# AutoTuner.net
KiCad netlist of a schematic drawn in EAGLE
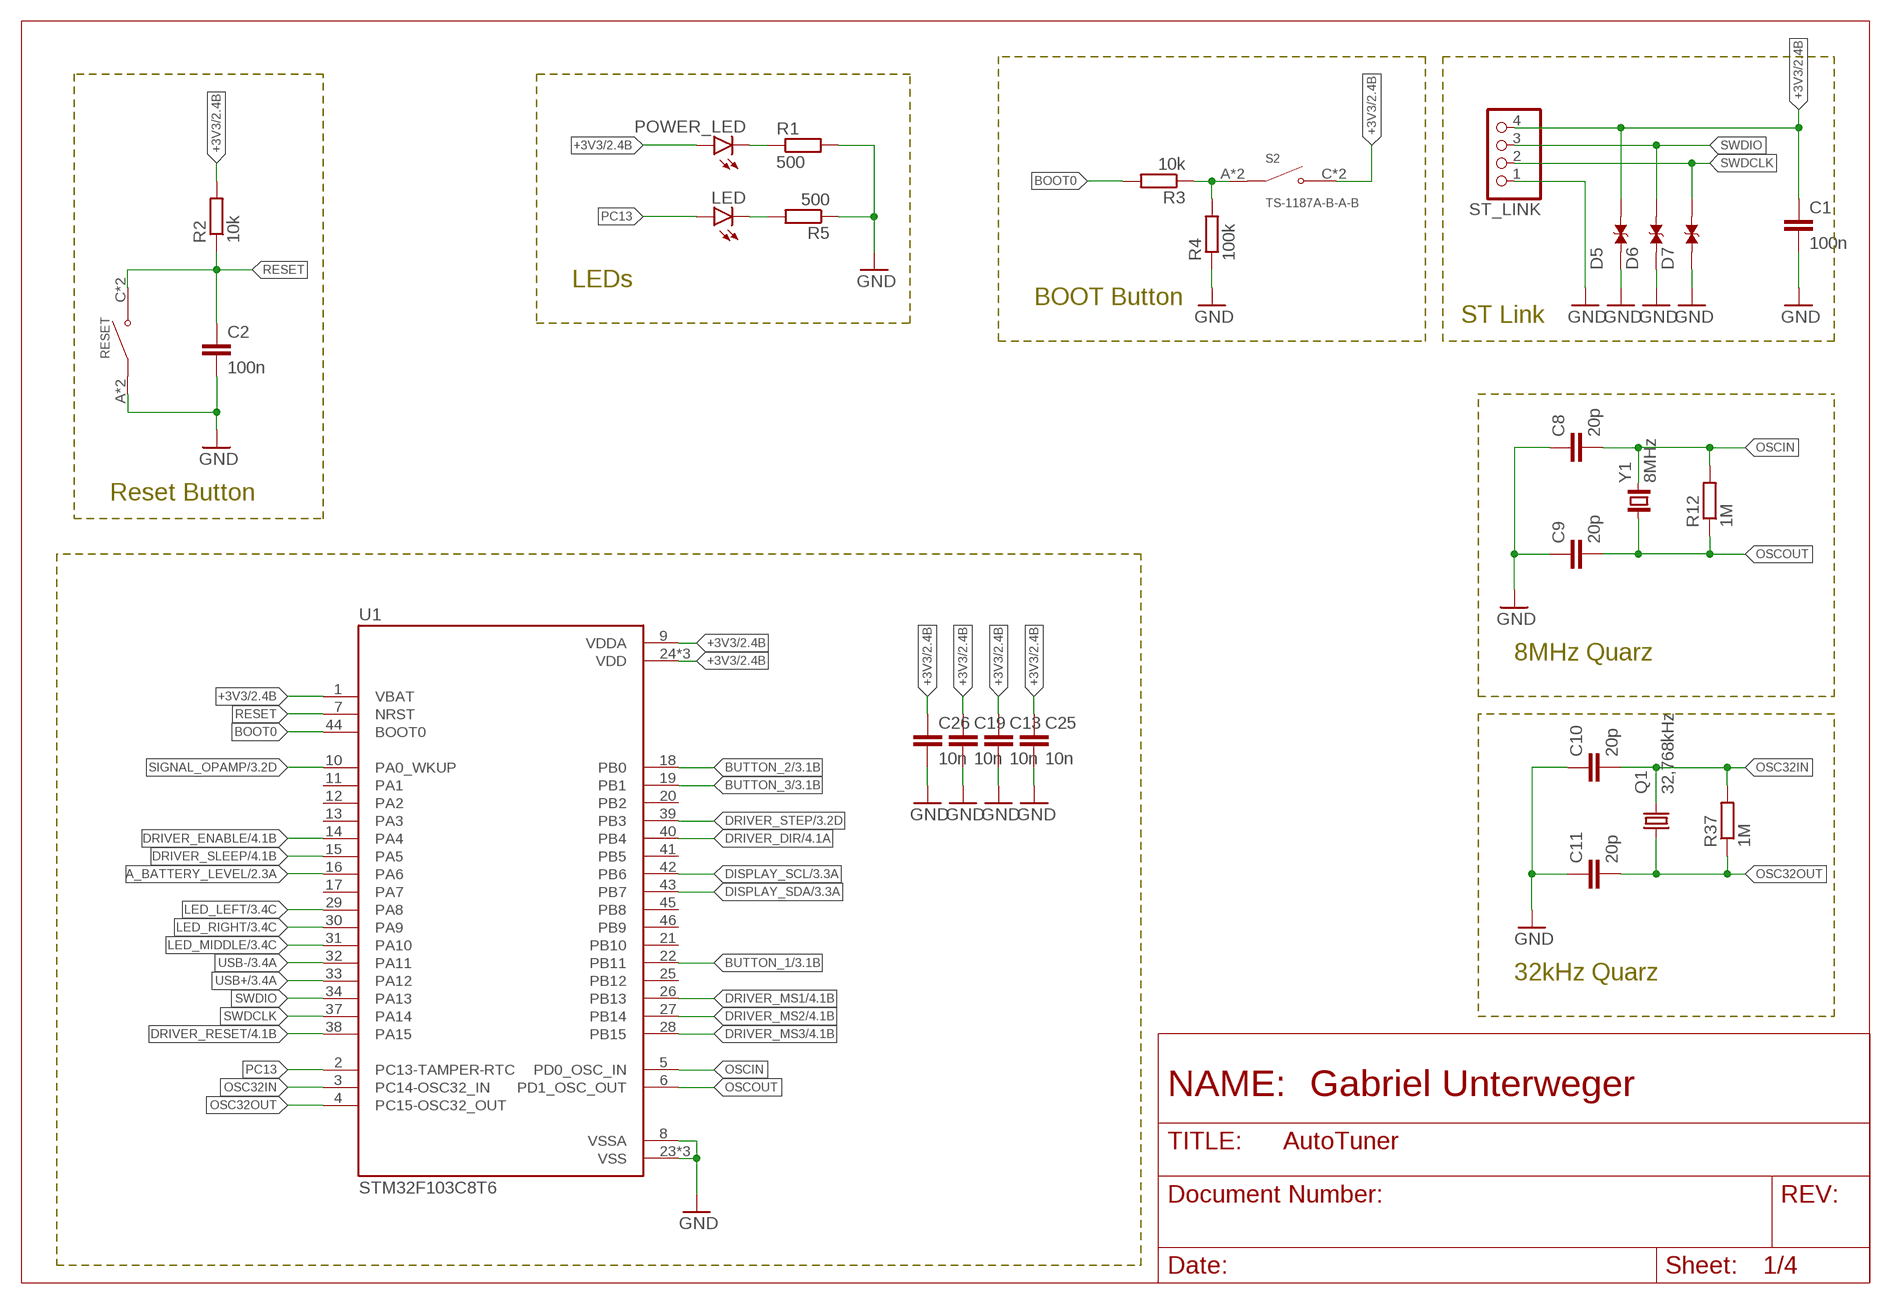
[diagram p0: schematic, sheet 1]
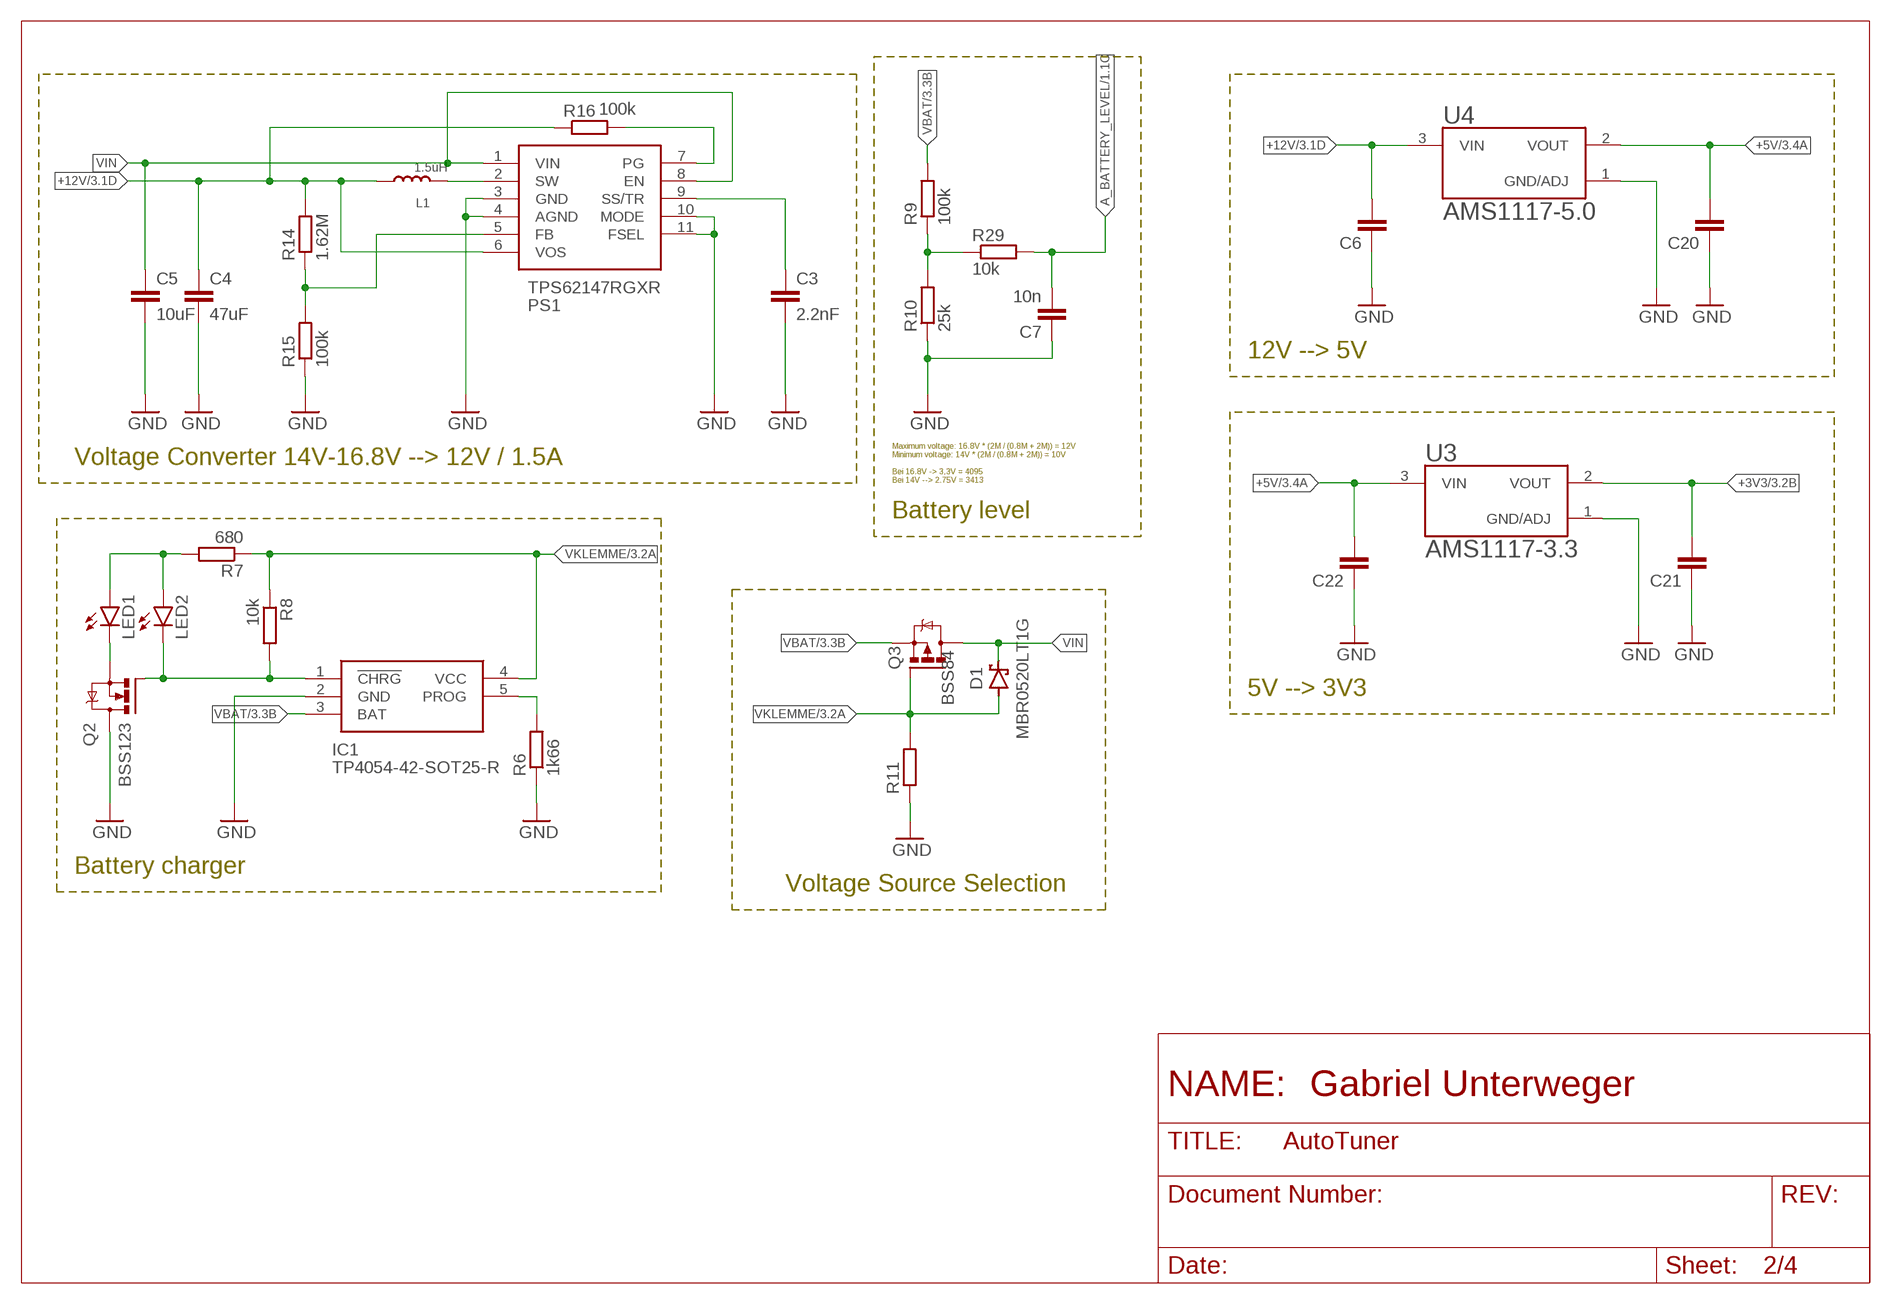
[diagram p1: schematic, sheet 2]
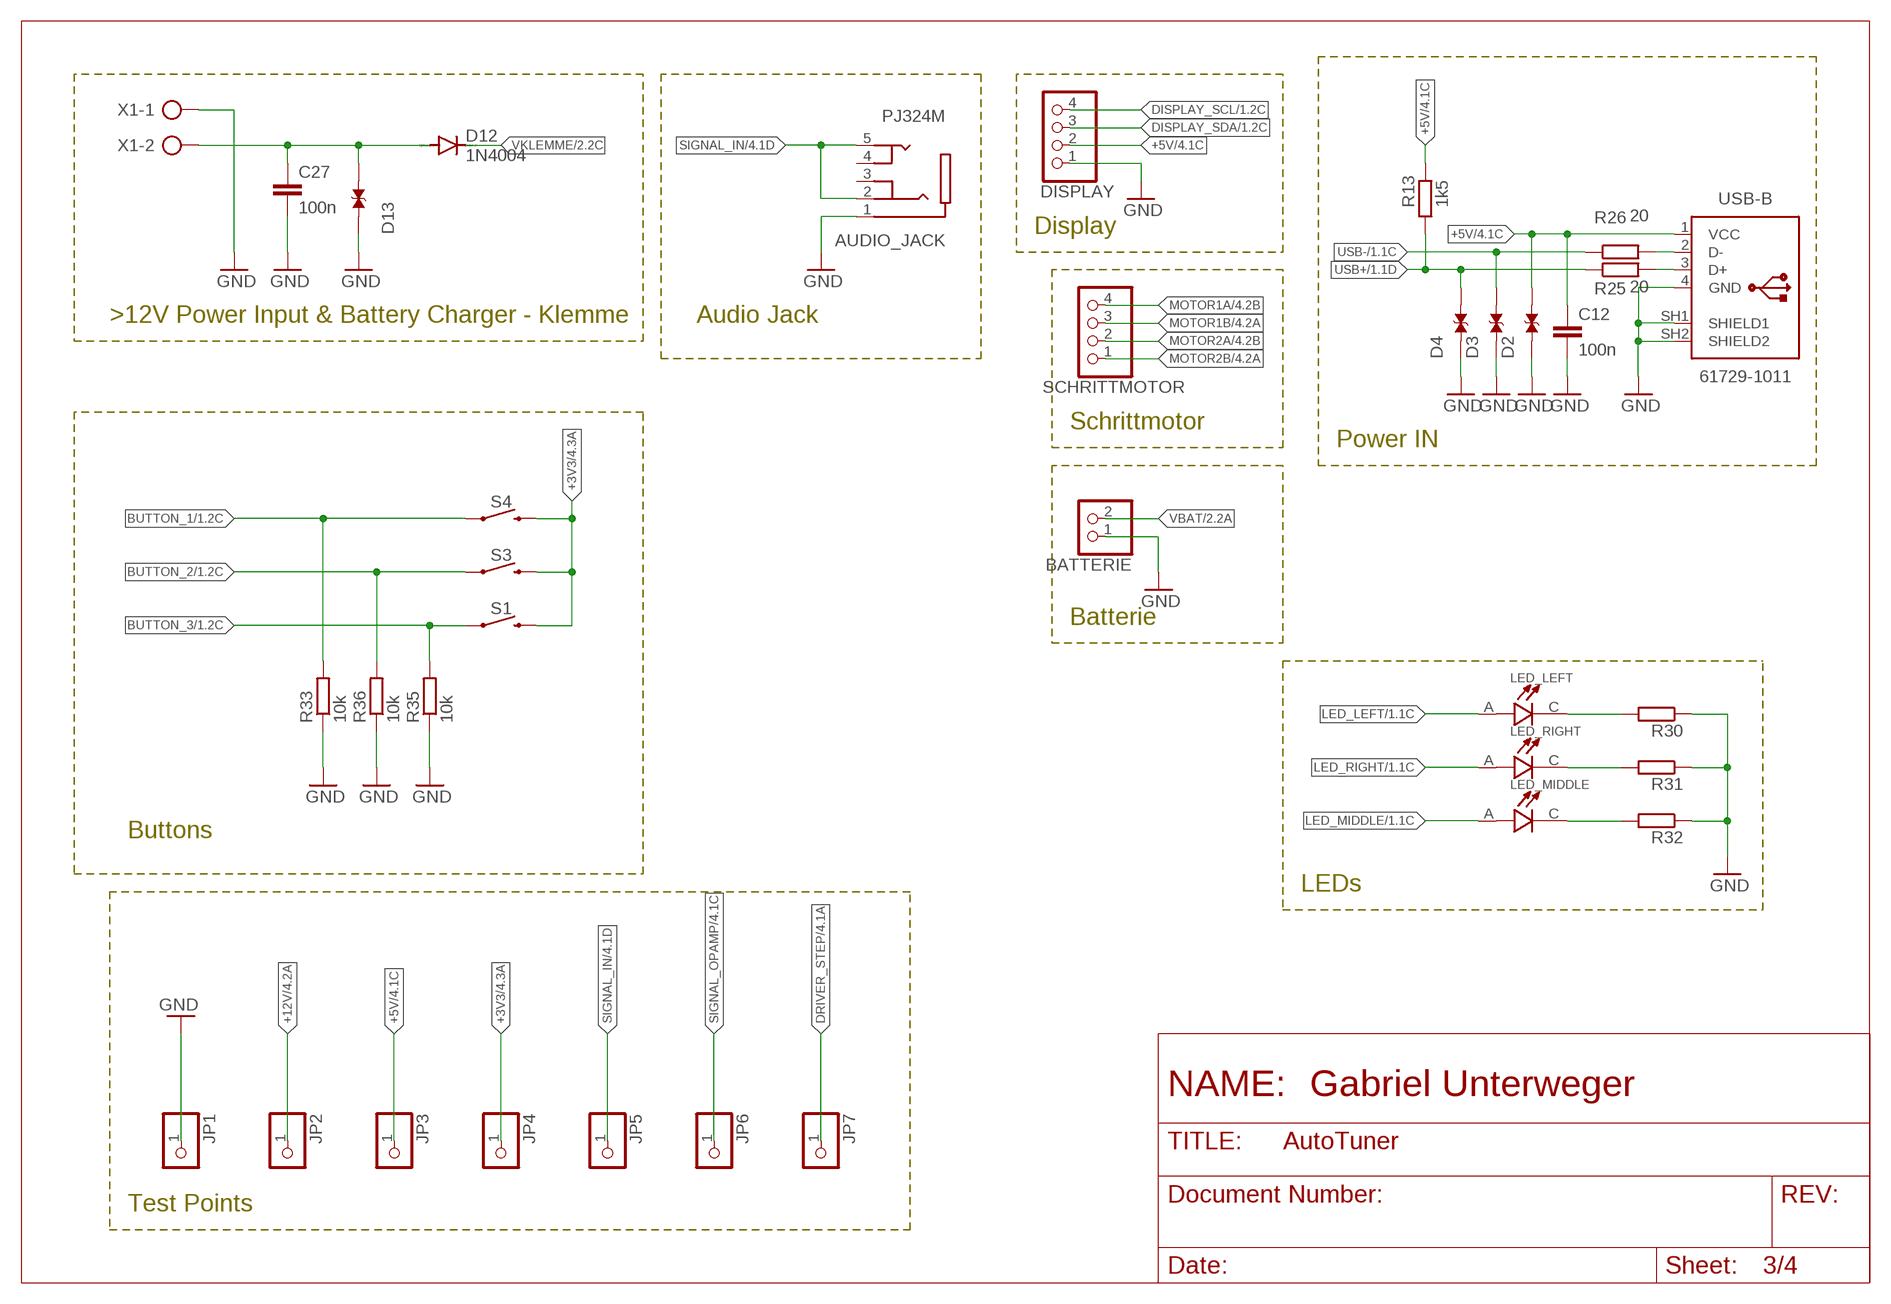
[diagram p2: schematic, sheet 3]
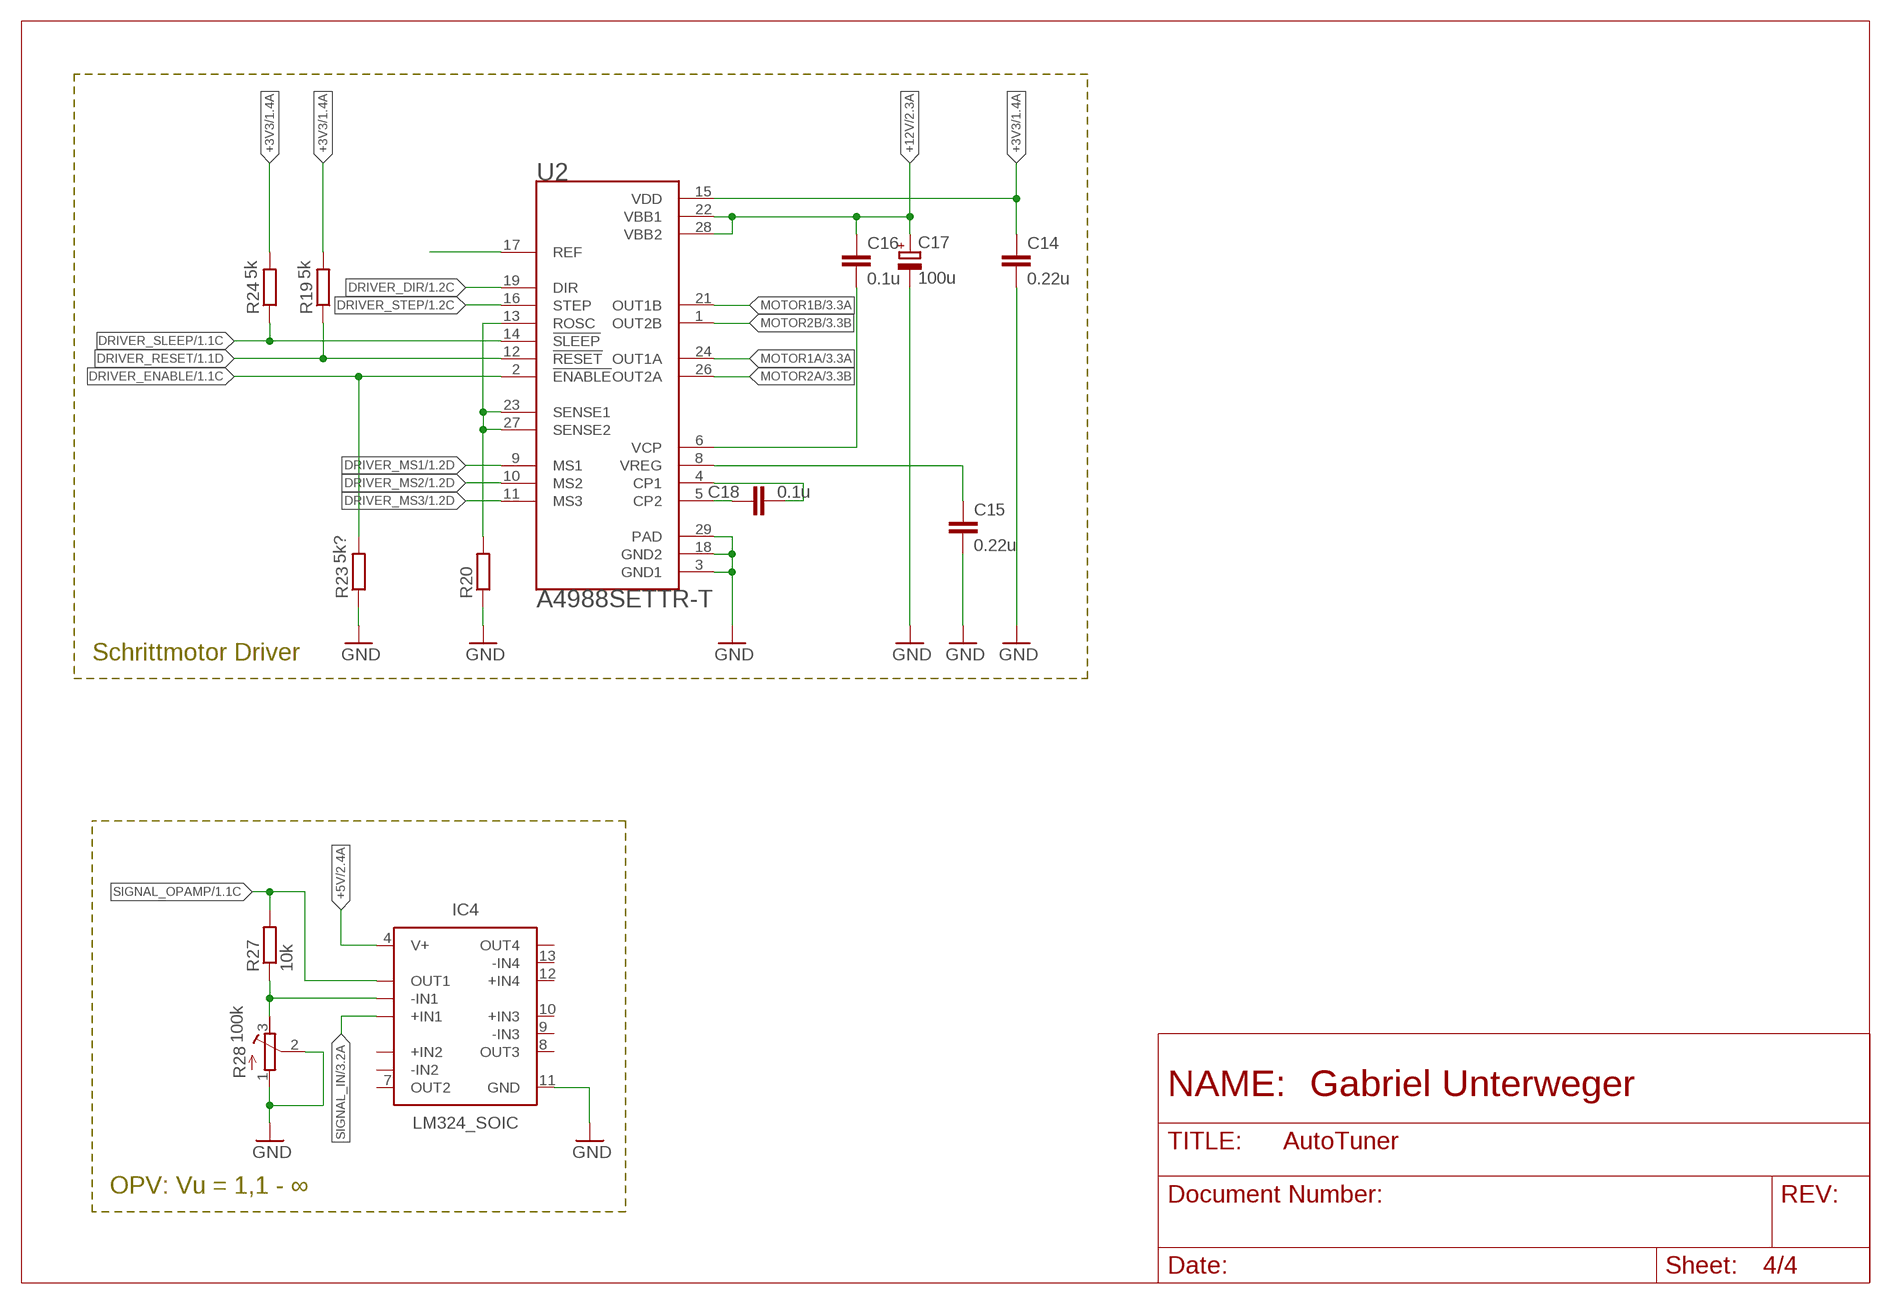
[diagram p3: schematic, sheet 4]

(export (version "E")
  (design (tool "Eeschema 10.0.6"))
  (components
    (comp (ref "C1")
      (value "100n")
      (footprint "eagle-import:C0805")
      (libsource (lib "eagle-import") (part "C-EUC0805"))
    )
    (comp (ref "C2")
      (value "100n")
      (footprint "eagle-import:C0805")
      (libsource (lib "eagle-import") (part "C-EUC0805"))
    )
    (comp (ref "C8")
      (value "20p")
      (footprint "eagle-import:C0805")
      (libsource (lib "eagle-import") (part "C-EUC0805"))
    )
    (comp (ref "C9")
      (value "20p")
      (footprint "eagle-import:C0805")
      (libsource (lib "eagle-import") (part "C-EUC0805"))
    )
    (comp (ref "C10")
      (value "20p")
      (footprint "eagle-import:C0805")
      (libsource (lib "eagle-import") (part "C-EUC0805"))
    )
    (comp (ref "C11")
      (value "20p")
      (footprint "eagle-import:C0805")
      (libsource (lib "eagle-import") (part "C-EUC0805"))
    )
    (comp (ref "C13")
      (value "10n")
      (footprint "eagle-import:C0805")
      (libsource (lib "eagle-import") (part "C-EUC0805"))
    )
    (comp (ref "C19")
      (value "10n")
      (footprint "eagle-import:C0805")
      (libsource (lib "eagle-import") (part "C-EUC0805"))
    )
    (comp (ref "C25")
      (value "10n")
      (footprint "eagle-import:C0805")
      (libsource (lib "eagle-import") (part "C-EUC0805"))
    )
    (comp (ref "C26")
      (value "10n")
      (footprint "eagle-import:C0805")
      (libsource (lib "eagle-import") (part "C-EUC0805"))
    )
    (comp (ref "D5")
      (value "TESD5V0L1UC_RJG")
      (footprint "eagle-import:DIO_TESD5V0L1UC_RJG")
      (fields (field (name "MF") "Taiwan Semiconductor Corporation") (field (name "MP") "TESD5V0L1UC RJG"))
      (libsource (lib "eagle-import") (part "TESD5V0L1UC_RJG"))
    )
    (comp (ref "D6")
      (value "TESD5V0L1UC_RJG")
      (footprint "eagle-import:DIO_TESD5V0L1UC_RJG")
      (fields (field (name "MF") "Taiwan Semiconductor Corporation") (field (name "MP") "TESD5V0L1UC RJG"))
      (libsource (lib "eagle-import") (part "TESD5V0L1UC_RJG"))
    )
    (comp (ref "D7")
      (value "TESD5V0L1UC_RJG")
      (footprint "eagle-import:DIO_TESD5V0L1UC_RJG")
      (fields
        (field (name "MF") "Taiwan Semiconductor Corporation")
        (field (name "MP") "TESD5V0L1UC RJG")
        (field (name "LCSC_PART") "C7420372")
      )
      (libsource (lib "eagle-import") (part "TESD5V0L1UC_RJG"))
    )
    (comp (ref "LED")
      (value "LEDCHIPLED_0805")
      (footprint "eagle-import:CHIPLED_0805")
      (libsource (lib "eagle-import") (part "LEDCHIPLED_0805"))
    )
    (comp (ref "POWER_LED")
      (value "LEDCHIPLED_0805")
      (footprint "eagle-import:CHIPLED_0805")
      (libsource (lib "eagle-import") (part "LEDCHIPLED_0805"))
    )
    (comp (ref "Q1")
      (value "32,768kHz")
      (footprint "eagle-import:3.2X1.5")
      (fields (field (name "LCSC_PART") "C32346"))
      (libsource (lib "eagle-import") (part "KX-327-NHF"))
    )
    (comp (ref "R1")
      (value "500")
      (footprint "eagle-import:R0805")
      (libsource (lib "eagle-import") (part "R-EU_R0805"))
    )
    (comp (ref "R2")
      (value "10k")
      (footprint "eagle-import:R0805")
      (libsource (lib "eagle-import") (part "R-EU_R0805"))
    )
    (comp (ref "R3")
      (value "10k")
      (footprint "eagle-import:R0805")
      (libsource (lib "eagle-import") (part "R-EU_R0805"))
    )
    (comp (ref "R4")
      (value "100k")
      (footprint "eagle-import:R0805")
      (libsource (lib "eagle-import") (part "R-EU_R0805"))
    )
    (comp (ref "R5")
      (value "500")
      (footprint "eagle-import:R0805")
      (libsource (lib "eagle-import") (part "R-EU_R0805"))
    )
    (comp (ref "R12")
      (value "1M")
      (footprint "eagle-import:R0805")
      (libsource (lib "eagle-import") (part "R-EU_R0805"))
    )
    (comp (ref "R37")
      (value "1M")
      (footprint "eagle-import:R0805")
      (libsource (lib "eagle-import") (part "R-EU_R0805"))
    )
    (comp (ref "RESET")
      (value "TS-1187A-B-A-B")
      (footprint "eagle-import:SW_TS-1187A-B-A-B")
      (fields (field (name "MF") "XKB Industrial Precision") (field (name "LCSC_PART") "C318884"))
      (libsource (lib "eagle-import") (part "TS-1187A-B-A-B"))
    )
    (comp (ref "S2")
      (value "TS-1187A-B-A-B")
      (footprint "eagle-import:SW_TS-1187A-B-A-B")
      (fields (field (name "MF") "XKB Industrial Precision") (field (name "LCSC_PART") "C318884"))
      (libsource (lib "eagle-import") (part "TS-1187A-B-A-B"))
    )
    (comp (ref "ST_LINK")
      (value "PINHD-1X4")
      (footprint "eagle-import:1X04")
      (libsource (lib "eagle-import") (part "PINHD-1X4"))
    )
    (comp (ref "U1")
      (value "STM32F103C8T6")
      (footprint "eagle-import:QFP50P900X900X160-48N")
      (fields (field (name "MF") "STMicroelectronics") (field (name "LCSC_PART") "C8734"))
      (libsource (lib "eagle-import") (part "STM32F103C8T6"))
    )
    (comp (ref "Y1")
      (value "8MHz")
      (footprint "eagle-import:CRYSTAL_2-SMD-5X3")
      (fields (field (name "LCSC_PART") "C115962"))
      (libsource (lib "eagle-import") (part "CRYSTAL_NX5032GA"))
    )
    (comp (ref "C14")
      (value "0.22u")
      (footprint "eagle-import:C0805")
      (libsource (lib "eagle-import") (part "C-EUC0805"))
    )
    (comp (ref "C15")
      (value "0.22u")
      (footprint "eagle-import:C0805")
      (libsource (lib "eagle-import") (part "C-EUC0805"))
    )
    (comp (ref "C16")
      (value "0.1u")
      (footprint "eagle-import:C0805")
      (libsource (lib "eagle-import") (part "C-EUC0805"))
    )
    (comp (ref "C17")
      (value "100u")
      (footprint "eagle-import:085CS_1AR")
      (libsource (lib "eagle-import") (part "CPOL-EU085CS-1AR"))
    )
    (comp (ref "C18")
      (value "0.1u")
      (footprint "eagle-import:C0805")
      (libsource (lib "eagle-import") (part "C-EUC0805"))
    )
    (comp (ref "IC4")
      (value "LM324_SOIC")
      (footprint "eagle-import:SOIC127P600X175-14N")
      (fields (field (name "MANUFACTURER") "Generic") (field (name "LCSC_PART") "C71035"))
      (libsource (lib "eagle-import") (part "LM324_SOIC"))
    )
    (comp (ref "R19")
      (value "5k")
      (footprint "eagle-import:R0805")
      (libsource (lib "eagle-import") (part "R-EU_R0805"))
    )
    (comp (ref "R20")
      (value "R-EU_R0805")
      (footprint "eagle-import:R0805")
      (libsource (lib "eagle-import") (part "R-EU_R0805"))
    )
    (comp (ref "R23")
      (value "5k?")
      (footprint "eagle-import:R0805")
      (libsource (lib "eagle-import") (part "R-EU_R0805"))
    )
    (comp (ref "R24")
      (value "5k")
      (footprint "eagle-import:R0805")
      (libsource (lib "eagle-import") (part "R-EU_R0805"))
    )
    (comp (ref "R27")
      (value "10k")
      (footprint "eagle-import:R0805")
      (libsource (lib "eagle-import") (part "R-EU_R0805"))
    )
    (comp (ref "R28")
      (value "100k")
      (footprint "eagle-import:RTRIM3296X")
      (libsource (lib "eagle-import") (part "R-TRIMM3296X"))
    )
    (comp (ref "U2")
      (value "A4988SETTR-T")
      (footprint "eagle-import:QFN50P500X500X90-29N")
      (fields (field (name "MF") "Allegro"))
      (libsource (lib "eagle-import") (part "A4988SETTR-T"))
    )
    (comp (ref "C3")
      (value "2.2nF")
      (footprint "eagle-import:C0805")
      (libsource (lib "eagle-import") (part "C-EUC0805"))
    )
    (comp (ref "C4")
      (value "47uF")
      (footprint "eagle-import:C0805")
      (libsource (lib "eagle-import") (part "C-EUC0805"))
    )
    (comp (ref "C5")
      (value "10uF")
      (footprint "eagle-import:C0805")
      (libsource (lib "eagle-import") (part "C-EUC0805"))
    )
    (comp (ref "C6")
      (value "C-EUC0805")
      (footprint "eagle-import:C0805")
      (libsource (lib "eagle-import") (part "C-EUC0805"))
    )
    (comp (ref "C7")
      (value "10n")
      (footprint "eagle-import:C0805")
      (libsource (lib "eagle-import") (part "C-EUC0805"))
    )
    (comp (ref "C20")
      (value "C-EUC0805")
      (footprint "eagle-import:C0805")
      (libsource (lib "eagle-import") (part "C-EUC0805"))
    )
    (comp (ref "C21")
      (value "C-EUC0805")
      (footprint "eagle-import:C0805")
      (libsource (lib "eagle-import") (part "C-EUC0805"))
    )
    (comp (ref "C22")
      (value "C-EUC0805")
      (footprint "eagle-import:C0805")
      (libsource (lib "eagle-import") (part "C-EUC0805"))
    )
    (comp (ref "D1")
      (value "MBR0520LT1G")
      (footprint "eagle-import:SODFL3718X115")
      (fields (field (name "MANUFACTURER") "ON Semiconductor") (field (name "LCSC_PART") "C191023"))
      (libsource (lib "eagle-import") (part "SCHOTTKY_DO-219MBR0520LT1G"))
    )
    (comp (ref "IC1")
      (value "TP4054-42-SOT25-R")
      (footprint "eagle-import:SOT95P280X100-5N")
      (fields (field (name "LCSC_PART") "C32574"))
      (libsource (lib "eagle-import") (part "TP4054-42-SOT25-R"))
    )
    (comp (ref "L1")
      (value "1.5uH")
      (footprint "eagle-import:PSPCAQ54")
      (fields (field (name "LCSC_PART") "C2686105"))
      (libsource (lib "eagle-import") (part "PSPCAQ54"))
    )
    (comp (ref "LED1")
      (value "LEDCHIPLED_0805")
      (footprint "eagle-import:CHIPLED_0805")
      (libsource (lib "eagle-import") (part "LEDCHIPLED_0805"))
    )
    (comp (ref "LED2")
      (value "LEDCHIPLED_0805")
      (footprint "eagle-import:CHIPLED_0805")
      (libsource (lib "eagle-import") (part "LEDCHIPLED_0805"))
    )
    (comp (ref "PS1")
      (value "TPS62147RGXR")
      (footprint "eagle-import:TPS621361RGXT")
      (fields (field (name "MOUSER_PART_NUMBER") "595-TPS62147RGXR"))
      (libsource (lib "eagle-import") (part "TPS62147RGXR"))
    )
    (comp (ref "Q2")
      (value "BSS123")
      (footprint "eagle-import:SOT23")
      (fields
        (field (name "MANUFACTURER") "ON Semiconductor")
        (field (name "MPN") "BSS123L")
        (field (name "LCSC_PART") "C20917")
      )
      (libsource (lib "eagle-import") (part "NMOSFET__SOT23-GSDBSS123"))
    )
    (comp (ref "Q3")
      (value "BSS84")
      (footprint "eagle-import:SOT23")
      (fields (field (name "MANUFACTURER") "ON Semiconductor"))
      (libsource (lib "eagle-import") (part "PMOSFET__SOT23-GSDBSS84"))
    )
    (comp (ref "R6")
      (value "1k66")
      (footprint "eagle-import:R0805")
      (libsource (lib "eagle-import") (part "R-EU_R0805"))
    )
    (comp (ref "R7")
      (value "680")
      (footprint "eagle-import:R0805")
      (libsource (lib "eagle-import") (part "R-EU_R0805"))
    )
    (comp (ref "R8")
      (value "10k")
      (footprint "eagle-import:R0805")
      (libsource (lib "eagle-import") (part "R-EU_R0805"))
    )
    (comp (ref "R9")
      (value "100k")
      (footprint "eagle-import:R0805")
      (libsource (lib "eagle-import") (part "R-EU_R0805"))
    )
    (comp (ref "R10")
      (value "25k")
      (footprint "eagle-import:R0805")
      (libsource (lib "eagle-import") (part "R-EU_R0805"))
    )
    (comp (ref "R11")
      (value "R-EU_R0805")
      (footprint "eagle-import:R0805")
      (libsource (lib "eagle-import") (part "R-EU_R0805"))
    )
    (comp (ref "R14")
      (value "1.62M")
      (footprint "eagle-import:R0805")
      (libsource (lib "eagle-import") (part "R-EU_R0805"))
    )
    (comp (ref "R15")
      (value "100k")
      (footprint "eagle-import:R0805")
      (libsource (lib "eagle-import") (part "R-EU_R0805"))
    )
    (comp (ref "R16")
      (value "100k")
      (footprint "eagle-import:R0805")
      (libsource (lib "eagle-import") (part "R-EU_R0805"))
    )
    (comp (ref "R29")
      (value "10k")
      (footprint "eagle-import:R0805")
      (libsource (lib "eagle-import") (part "R-EU_R0805"))
    )
    (comp (ref "U3")
      (value "AMS1117-3.3")
      (footprint "eagle-import:SOT229P700X180-4N")
      (fields (field (name "MF") "Advanced Monolithic Systems") (field (name "LCSC_PART") "C6186"))
      (libsource (lib "eagle-import") (part "AMS1117-3.3"))
    )
    (comp (ref "U4")
      (value "AMS1117-5.0")
      (footprint "eagle-import:SOT229P700X180-4N")
      (fields (field (name "MF") "Advanced Monolithic Systems") (field (name "LCSC_PART") "C6187"))
      (libsource (lib "eagle-import") (part "AMS1117-5.0"))
    )
    (comp (ref "AUDIO_JACK")
      (value "PJ324M")
      (footprint "eagle-import:WENZHOU_PJ324M")
      (fields (field (name "MF") "Wenzhou QingPu Electronics Co.Ltd"))
      (libsource (lib "eagle-import") (part "PJ324M"))
    )
    (comp (ref "BATTERIE")
      (value "PINHD-1X2")
      (footprint "eagle-import:1X02")
      (libsource (lib "eagle-import") (part "PINHD-1X2"))
    )
    (comp (ref "C12")
      (value "100n")
      (footprint "eagle-import:C0805")
      (libsource (lib "eagle-import") (part "C-EUC0805"))
    )
    (comp (ref "C27")
      (value "100n")
      (footprint "eagle-import:C0805")
      (libsource (lib "eagle-import") (part "C-EUC0805"))
    )
    (comp (ref "D2")
      (value "TESD5V0L1UC_RJG")
      (footprint "eagle-import:DIO_TESD5V0L1UC_RJG")
      (fields (field (name "MF") "Taiwan Semiconductor Corporation") (field (name "MP") "TESD5V0L1UC RJG"))
      (libsource (lib "eagle-import") (part "TESD5V0L1UC_RJG"))
    )
    (comp (ref "D3")
      (value "TESD5V0L1UC_RJG")
      (footprint "eagle-import:DIO_TESD5V0L1UC_RJG")
      (fields (field (name "MF") "Taiwan Semiconductor Corporation") (field (name "MP") "TESD5V0L1UC RJG"))
      (libsource (lib "eagle-import") (part "TESD5V0L1UC_RJG"))
    )
    (comp (ref "D4")
      (value "TESD5V0L1UC_RJG")
      (footprint "eagle-import:DIO_TESD5V0L1UC_RJG")
      (fields (field (name "MF") "Taiwan Semiconductor Corporation") (field (name "MP") "TESD5V0L1UC RJG"))
      (libsource (lib "eagle-import") (part "TESD5V0L1UC_RJG"))
    )
    (comp (ref "D12")
      (value "1N4004")
      (footprint "eagle-import:DO41-10")
      (libsource (lib "eagle-import") (part "1N4004"))
    )
    (comp (ref "D13")
      (value "TESD5V0L1UC_RJG")
      (footprint "eagle-import:DIO_TESD5V0L1UC_RJG")
      (fields (field (name "MF") "Taiwan Semiconductor Corporation") (field (name "MP") "TESD5V0L1UC RJG"))
      (libsource (lib "eagle-import") (part "TESD5V0L1UC_RJG"))
    )
    (comp (ref "DISPLAY")
      (value "PINHD-1X4")
      (footprint "eagle-import:1X04")
      (libsource (lib "eagle-import") (part "PINHD-1X4"))
    )
    (comp (ref "JP1")
      (value "PINHD-1X1")
      (footprint "eagle-import:1X01")
      (libsource (lib "eagle-import") (part "PINHD-1X1"))
    )
    (comp (ref "JP2")
      (value "PINHD-1X1")
      (footprint "eagle-import:1X01")
      (libsource (lib "eagle-import") (part "PINHD-1X1"))
    )
    (comp (ref "JP3")
      (value "PINHD-1X1")
      (footprint "eagle-import:1X01")
      (libsource (lib "eagle-import") (part "PINHD-1X1"))
    )
    (comp (ref "JP4")
      (value "PINHD-1X1")
      (footprint "eagle-import:1X01")
      (libsource (lib "eagle-import") (part "PINHD-1X1"))
    )
    (comp (ref "JP5")
      (value "PINHD-1X1")
      (footprint "eagle-import:1X01")
      (libsource (lib "eagle-import") (part "PINHD-1X1"))
    )
    (comp (ref "JP6")
      (value "PINHD-1X1")
      (footprint "eagle-import:1X01")
      (libsource (lib "eagle-import") (part "PINHD-1X1"))
    )
    (comp (ref "JP7")
      (value "PINHD-1X1")
      (footprint "eagle-import:1X01")
      (libsource (lib "eagle-import") (part "PINHD-1X1"))
    )
    (comp (ref "LED_LEFT")
      (value "L-53GD")
      (footprint "eagle-import:LEDRD254W50D500H1060")
      (fields (field (name "MF") "Kingbright"))
      (libsource (lib "eagle-import") (part "L-53GD"))
    )
    (comp (ref "LED_MIDDLE")
      (value "L-53GD")
      (footprint "eagle-import:LEDRD254W50D500H1060")
      (fields (field (name "MF") "Kingbright"))
      (libsource (lib "eagle-import") (part "L-53GD"))
    )
    (comp (ref "LED_RIGHT")
      (value "L-53GD")
      (footprint "eagle-import:LEDRD254W50D500H1060")
      (fields (field (name "MF") "Kingbright"))
      (libsource (lib "eagle-import") (part "L-53GD"))
    )
    (comp (ref "R13")
      (value "1k5")
      (footprint "eagle-import:R0805")
      (libsource (lib "eagle-import") (part "R-EU_R0805"))
    )
    (comp (ref "R25")
      (value "20")
      (footprint "eagle-import:R0805")
      (libsource (lib "eagle-import") (part "R-EU_R0805"))
    )
    (comp (ref "R26")
      (value "20")
      (footprint "eagle-import:R0805")
      (libsource (lib "eagle-import") (part "R-EU_R0805"))
    )
    (comp (ref "R30")
      (value "R-EU_R0805")
      (footprint "eagle-import:R0805")
      (libsource (lib "eagle-import") (part "R-EU_R0805"))
    )
    (comp (ref "R31")
      (value "R-EU_R0805")
      (footprint "eagle-import:R0805")
      (libsource (lib "eagle-import") (part "R-EU_R0805"))
    )
    (comp (ref "R32")
      (value "R-EU_R0805")
      (footprint "eagle-import:R0805")
      (libsource (lib "eagle-import") (part "R-EU_R0805"))
    )
    (comp (ref "R33")
      (value "10k")
      (footprint "eagle-import:R0805")
      (libsource (lib "eagle-import") (part "R-EU_R0805"))
    )
    (comp (ref "R35")
      (value "10k")
      (footprint "eagle-import:R0805")
      (libsource (lib "eagle-import") (part "R-EU_R0805"))
    )
    (comp (ref "R36")
      (value "10k")
      (footprint "eagle-import:R0805")
      (libsource (lib "eagle-import") (part "R-EU_R0805"))
    )
    (comp (ref "S1")
      (value "MOMENTARY-SWITCH-SPST-PTH-12MM")
      (footprint "eagle-import:TACTILE_SWITCH_PTH_12MM")
      (libsource (lib "eagle-import") (part "MOMENTARY-SWITCH-SPST-PTH-12MM"))
    )
    (comp (ref "S3")
      (value "MOMENTARY-SWITCH-SPST-PTH-12MM")
      (footprint "eagle-import:TACTILE_SWITCH_PTH_12MM")
      (libsource (lib "eagle-import") (part "MOMENTARY-SWITCH-SPST-PTH-12MM"))
    )
    (comp (ref "S4")
      (value "MOMENTARY-SWITCH-SPST-PTH-12MM")
      (footprint "eagle-import:TACTILE_SWITCH_PTH_12MM")
      (libsource (lib "eagle-import") (part "MOMENTARY-SWITCH-SPST-PTH-12MM"))
    )
    (comp (ref "SCHRITTMOTOR")
      (value "PINHD-1X4")
      (footprint "eagle-import:1X04")
      (libsource (lib "eagle-import") (part "PINHD-1X4"))
    )
    (comp (ref "USB-B")
      (value "61729-1011")
      (footprint "eagle-import:61729-1011BLF")
      (fields (field (name "MANUFACTURER") "Amphenol ICC (FCI)") (field (name "MPN") "61729-1011BLF"))
      (libsource (lib "eagle-import") (part "61729-1011"))
    )
    (comp (ref "X1")
      (value "AK300/2")
      (footprint "eagle-import:AK300_2")
      (libsource (lib "eagle-import") (part "AK300/2"))
    )
  )
  (nets
    (net (code "1") (name "+3V3") (class "Default")
      (node (ref "C1") (pin "1") (pinfunction "1_1") (pintype "passive"))
      (node (ref "C13") (pin "1") (pinfunction "1_1") (pintype "passive"))
      (node (ref "C14") (pin "1") (pinfunction "1_1") (pintype "passive"))
      (node (ref "C19") (pin "1") (pinfunction "1_1") (pintype "passive"))
      (node (ref "C21") (pin "2") (pinfunction "2_2") (pintype "passive"))
      (node (ref "C25") (pin "1") (pinfunction "1_1") (pintype "passive"))
      (node (ref "C26") (pin "1") (pinfunction "1_1") (pintype "passive"))
      (node (ref "D5") (pin "2") (pinfunction "2_2") (pintype "passive"))
      (node (ref "JP4") (pin "1") (pinfunction "1_1") (pintype "passive"))
      (node (ref "POWER_LED") (pin "A") (pinfunction "A_A") (pintype "passive"))
      (node (ref "R19") (pin "2") (pinfunction "2_2") (pintype "passive"))
      (node (ref "R2") (pin "2") (pinfunction "2_2") (pintype "passive"))
      (node (ref "R24") (pin "2") (pinfunction "2_2") (pintype "passive"))
      (node (ref "S1") (pin "3") (pinfunction "2_3") (pintype "passive"))
      (node (ref "S2") (pin "C") (pinfunction "NO_C") (pintype "passive"))
      (node (ref "S2") (pin "D") (pinfunction "NO_D") (pintype "passive"))
      (node (ref "S3") (pin "3") (pinfunction "2_3") (pintype "passive"))
      (node (ref "S4") (pin "3") (pinfunction "2_3") (pintype "passive"))
      (node (ref "ST_LINK") (pin "4") (pinfunction "4_4") (pintype "passive"))
      (node (ref "U1") (pin "1") (pinfunction "VBAT_1") (pintype "bidirectional"))
      (node (ref "U1") (pin "24") (pinfunction "VDD_24") (pintype "power_in"))
      (node (ref "U1") (pin "36") (pinfunction "VDD_36") (pintype "power_in"))
      (node (ref "U1") (pin "48") (pinfunction "VDD_48") (pintype "power_in"))
      (node (ref "U1") (pin "9") (pinfunction "VDDA_9") (pintype "power_in"))
      (node (ref "U2") (pin "15") (pinfunction "VDD_15") (pintype "power_in"))
      (node (ref "U3") (pin "2") (pinfunction "VOUT_2") (pintype "output"))
    )
    (net (code "2") (name "+5V") (class "Default")
      (node (ref "C12") (pin "1") (pinfunction "1_1") (pintype "passive"))
      (node (ref "C20") (pin "2") (pinfunction "2_2") (pintype "passive"))
      (node (ref "C22") (pin "2") (pinfunction "2_2") (pintype "passive"))
      (node (ref "D2") (pin "2") (pinfunction "2_2") (pintype "passive"))
      (node (ref "DISPLAY") (pin "2") (pinfunction "2_2") (pintype "passive"))
      (node (ref "IC4") (pin "4") (pinfunction "V+_4") (pintype "passive"))
      (node (ref "JP3") (pin "1") (pinfunction "1_1") (pintype "passive"))
      (node (ref "R13") (pin "2") (pinfunction "2_2") (pintype "passive"))
      (node (ref "U3") (pin "3") (pinfunction "VIN_3") (pintype "input"))
      (node (ref "U4") (pin "2") (pinfunction "VOUT_2") (pintype "output"))
      (node (ref "USB-B") (pin "1") (pinfunction "VCC_1") (pintype "power_in"))
    )
    (net (code "3") (name "+12V") (class "Default")
      (node (ref "C16") (pin "1") (pinfunction "1_1") (pintype "passive"))
      (node (ref "C17") (pin "+") (pinfunction "+_+") (pintype "passive"))
      (node (ref "C4") (pin "1") (pinfunction "1_1") (pintype "passive"))
      (node (ref "C6") (pin "2") (pinfunction "2_2") (pintype "passive"))
      (node (ref "JP2") (pin "1") (pinfunction "1_1") (pintype "passive"))
      (node (ref "L1") (pin "1") (pinfunction "1_1") (pintype "bidirectional"))
      (node (ref "PS1") (pin "6") (pinfunction "VOS_6") (pintype "bidirectional"))
      (node (ref "R14") (pin "2") (pinfunction "2_2") (pintype "passive"))
      (node (ref "R16") (pin "1") (pinfunction "1_1") (pintype "passive"))
      (node (ref "U2") (pin "22") (pinfunction "VBB1_22") (pintype "power_in"))
      (node (ref "U2") (pin "28") (pinfunction "VBB2_28") (pintype "power_in"))
      (node (ref "U4") (pin "3") (pinfunction "VIN_3") (pintype "input"))
    )
    (net (code "4") (name "A_BATTERY_LEVEL") (class "Default")
      (node (ref "C7") (pin "2") (pinfunction "2_2") (pintype "passive"))
      (node (ref "R29") (pin "2") (pinfunction "2_2") (pintype "passive"))
      (node (ref "U1") (pin "16") (pinfunction "PA6_16") (pintype "bidirectional"))
    )
    (net (code "5") (name "BOOT0") (class "Default")
      (node (ref "R3") (pin "2") (pinfunction "2_2") (pintype "passive"))
      (node (ref "U1") (pin "44") (pinfunction "BOOT0_44") (pintype "input"))
    )
    (net (code "6") (name "BUTTON_1") (class "Default")
      (node (ref "R33") (pin "2") (pinfunction "2_2") (pintype "passive"))
      (node (ref "S4") (pin "1") (pinfunction "1_1") (pintype "passive"))
      (node (ref "U1") (pin "22") (pinfunction "PB11_22") (pintype "bidirectional"))
    )
    (net (code "7") (name "BUTTON_2") (class "Default")
      (node (ref "R36") (pin "2") (pinfunction "2_2") (pintype "passive"))
      (node (ref "S3") (pin "1") (pinfunction "1_1") (pintype "passive"))
      (node (ref "U1") (pin "18") (pinfunction "PB0_18") (pintype "bidirectional"))
    )
    (net (code "8") (name "BUTTON_3") (class "Default")
      (node (ref "R35") (pin "2") (pinfunction "2_2") (pintype "passive"))
      (node (ref "S1") (pin "1") (pinfunction "1_1") (pintype "passive"))
      (node (ref "U1") (pin "19") (pinfunction "PB1_19") (pintype "bidirectional"))
    )
    (net (code "9") (name "DISPLAY_SCL") (class "Default")
      (node (ref "DISPLAY") (pin "4") (pinfunction "4_4") (pintype "passive"))
      (node (ref "U1") (pin "42") (pinfunction "PB6_42") (pintype "bidirectional"))
    )
    (net (code "10") (name "DISPLAY_SDA") (class "Default")
      (node (ref "DISPLAY") (pin "3") (pinfunction "3_3") (pintype "passive"))
      (node (ref "U1") (pin "43") (pinfunction "PB7_43") (pintype "bidirectional"))
    )
    (net (code "11") (name "DRIVER_DIR") (class "Default")
      (node (ref "U1") (pin "40") (pinfunction "PB4_40") (pintype "bidirectional"))
      (node (ref "U2") (pin "19") (pinfunction "DIR_19") (pintype "input"))
    )
    (net (code "12") (name "DRIVER_ENABLE") (class "Default")
      (node (ref "R23") (pin "2") (pinfunction "2_2") (pintype "passive"))
      (node (ref "U1") (pin "14") (pinfunction "PA4_14") (pintype "bidirectional"))
      (node (ref "U2") (pin "2") (pinfunction "~{ENABLE}_2") (pintype "input"))
    )
    (net (code "13") (name "DRIVER_MS1") (class "Default")
      (node (ref "U1") (pin "26") (pinfunction "PB13_26") (pintype "bidirectional"))
      (node (ref "U2") (pin "9") (pinfunction "MS1_9") (pintype "input"))
    )
    (net (code "14") (name "DRIVER_MS2") (class "Default")
      (node (ref "U1") (pin "27") (pinfunction "PB14_27") (pintype "bidirectional"))
      (node (ref "U2") (pin "10") (pinfunction "MS2_10") (pintype "input"))
    )
    (net (code "15") (name "DRIVER_MS3") (class "Default")
      (node (ref "U1") (pin "28") (pinfunction "PB15_28") (pintype "bidirectional"))
      (node (ref "U2") (pin "11") (pinfunction "MS3_11") (pintype "input"))
    )
    (net (code "16") (name "DRIVER_RESET") (class "Default")
      (node (ref "R19") (pin "1") (pinfunction "1_1") (pintype "passive"))
      (node (ref "U1") (pin "38") (pinfunction "PA15_38") (pintype "bidirectional"))
      (node (ref "U2") (pin "12") (pinfunction "~{RESET}_12") (pintype "input"))
    )
    (net (code "17") (name "DRIVER_SLEEP") (class "Default")
      (node (ref "R24") (pin "1") (pinfunction "1_1") (pintype "passive"))
      (node (ref "U1") (pin "15") (pinfunction "PA5_15") (pintype "bidirectional"))
      (node (ref "U2") (pin "14") (pinfunction "~{SLEEP}_14") (pintype "input"))
    )
    (net (code "18") (name "DRIVER_STEP") (class "Default")
      (node (ref "JP7") (pin "1") (pinfunction "1_1") (pintype "passive"))
      (node (ref "U1") (pin "39") (pinfunction "PB3_39") (pintype "bidirectional"))
      (node (ref "U2") (pin "16") (pinfunction "STEP_16") (pintype "input"))
    )
    (net (code "19") (name "GND") (class "Default")
      (node (ref "AUDIO_JACK") (pin "1") (pinfunction "SLEEVE_1") (pintype "passive"))
      (node (ref "BATTERIE") (pin "1") (pinfunction "1_1") (pintype "passive"))
      (node (ref "C1") (pin "2") (pinfunction "2_2") (pintype "passive"))
      (node (ref "C10") (pin "1") (pinfunction "1_1") (pintype "passive"))
      (node (ref "C11") (pin "1") (pinfunction "1_1") (pintype "passive"))
      (node (ref "C12") (pin "2") (pinfunction "2_2") (pintype "passive"))
      (node (ref "C13") (pin "2") (pinfunction "2_2") (pintype "passive"))
      (node (ref "C14") (pin "2") (pinfunction "2_2") (pintype "passive"))
      (node (ref "C15") (pin "2") (pinfunction "2_2") (pintype "passive"))
      (node (ref "C17") (pin "-") (pinfunction "-_-") (pintype "passive"))
      (node (ref "C19") (pin "2") (pinfunction "2_2") (pintype "passive"))
      (node (ref "C2") (pin "2") (pinfunction "2_2") (pintype "passive"))
      (node (ref "C20") (pin "1") (pinfunction "1_1") (pintype "passive"))
      (node (ref "C21") (pin "1") (pinfunction "1_1") (pintype "passive"))
      (node (ref "C22") (pin "1") (pinfunction "1_1") (pintype "passive"))
      (node (ref "C25") (pin "2") (pinfunction "2_2") (pintype "passive"))
      (node (ref "C26") (pin "2") (pinfunction "2_2") (pintype "passive"))
      (node (ref "C27") (pin "2") (pinfunction "2_2") (pintype "passive"))
      (node (ref "C3") (pin "2") (pinfunction "2_2") (pintype "passive"))
      (node (ref "C4") (pin "2") (pinfunction "2_2") (pintype "passive"))
      (node (ref "C5") (pin "2") (pinfunction "2_2") (pintype "passive"))
      (node (ref "C6") (pin "1") (pinfunction "1_1") (pintype "passive"))
      (node (ref "C7") (pin "1") (pinfunction "1_1") (pintype "passive"))
      (node (ref "C8") (pin "1") (pinfunction "1_1") (pintype "passive"))
      (node (ref "C9") (pin "1") (pinfunction "1_1") (pintype "passive"))
      (node (ref "D13") (pin "1") (pinfunction "1_1") (pintype "passive"))
      (node (ref "D2") (pin "1") (pinfunction "1_1") (pintype "passive"))
      (node (ref "D3") (pin "1") (pinfunction "1_1") (pintype "passive"))
      (node (ref "D4") (pin "1") (pinfunction "1_1") (pintype "passive"))
      (node (ref "D5") (pin "1") (pinfunction "1_1") (pintype "passive"))
      (node (ref "D6") (pin "1") (pinfunction "1_1") (pintype "passive"))
      (node (ref "D7") (pin "1") (pinfunction "1_1") (pintype "passive"))
      (node (ref "DISPLAY") (pin "1") (pinfunction "1_1") (pintype "passive"))
      (node (ref "IC1") (pin "2") (pinfunction "GND_2") (pintype "bidirectional"))
      (node (ref "IC4") (pin "11") (pinfunction "GND_11") (pintype "passive"))
      (node (ref "JP1") (pin "1") (pinfunction "1_1") (pintype "passive"))
      (node (ref "PS1") (pin "10") (pinfunction "MODE_10") (pintype "bidirectional"))
      (node (ref "PS1") (pin "11") (pinfunction "FSEL_11") (pintype "bidirectional"))
      (node (ref "PS1") (pin "3") (pinfunction "GND_3") (pintype "bidirectional"))
      (node (ref "PS1") (pin "4") (pinfunction "AGND_4") (pintype "bidirectional"))
      (node (ref "Q2") (pin "3") (pinfunction "D_3") (pintype "passive"))
      (node (ref "R1") (pin "2") (pinfunction "2_2") (pintype "passive"))
      (node (ref "R10") (pin "1") (pinfunction "1_1") (pintype "passive"))
      (node (ref "R11") (pin "1") (pinfunction "1_1") (pintype "passive"))
      (node (ref "R15") (pin "1") (pinfunction "1_1") (pintype "passive"))
      (node (ref "R20") (pin "1") (pinfunction "1_1") (pintype "passive"))
      (node (ref "R23") (pin "1") (pinfunction "1_1") (pintype "passive"))
      (node (ref "R28") (pin "1") (pinfunction "A_1") (pintype "passive"))
      (node (ref "R28") (pin "2") (pinfunction "S_2") (pintype "passive"))
      (node (ref "R30") (pin "1") (pinfunction "1_1") (pintype "passive"))
      (node (ref "R31") (pin "1") (pinfunction "1_1") (pintype "passive"))
      (node (ref "R32") (pin "1") (pinfunction "1_1") (pintype "passive"))
      (node (ref "R33") (pin "1") (pinfunction "1_1") (pintype "passive"))
      (node (ref "R35") (pin "1") (pinfunction "1_1") (pintype "passive"))
      (node (ref "R36") (pin "1") (pinfunction "1_1") (pintype "passive"))
      (node (ref "R4") (pin "1") (pinfunction "1_1") (pintype "passive"))
      (node (ref "R5") (pin "1") (pinfunction "1_1") (pintype "passive"))
      (node (ref "R6") (pin "1") (pinfunction "1_1") (pintype "passive"))
      (node (ref "RESET") (pin "A") (pinfunction "COM_A") (pintype "passive"))
      (node (ref "RESET") (pin "B") (pinfunction "COM_B") (pintype "passive"))
      (node (ref "ST_LINK") (pin "1") (pinfunction "1_1") (pintype "passive"))
      (node (ref "U1") (pin "23") (pinfunction "VSS_23") (pintype "power_in"))
      (node (ref "U1") (pin "35") (pinfunction "VSS_35") (pintype "power_in"))
      (node (ref "U1") (pin "47") (pinfunction "VSS_47") (pintype "power_in"))
      (node (ref "U1") (pin "8") (pinfunction "VSSA_8") (pintype "power_in"))
      (node (ref "U2") (pin "18") (pinfunction "GND2_18") (pintype "passive"))
      (node (ref "U2") (pin "29") (pinfunction "PAD_29") (pintype "passive"))
      (node (ref "U2") (pin "3") (pinfunction "GND1_3") (pintype "passive"))
      (node (ref "U3") (pin "1") (pinfunction "GND/ADJ_1") (pintype "power_in"))
      (node (ref "U4") (pin "1") (pinfunction "GND/ADJ_1") (pintype "power_in"))
      (node (ref "USB-B") (pin "4") (pinfunction "GND_4") (pintype "power_in"))
      (node (ref "USB-B") (pin "SH1") (pinfunction "SHIELD1_SH1") (pintype "power_in"))
      (node (ref "USB-B") (pin "SH2") (pinfunction "SHIELD2_SH2") (pintype "power_in"))
      (node (ref "X1") (pin "1") (pinfunction "KL_1") (pintype "passive"))
    )
    (net (code "20") (name "LED_LEFT") (class "Default")
      (node (ref "LED_LEFT") (pin "A") (pinfunction "A_A") (pintype "passive"))
      (node (ref "U1") (pin "29") (pinfunction "PA8_29") (pintype "bidirectional"))
    )
    (net (code "21") (name "LED_MIDDLE") (class "Default")
      (node (ref "LED_MIDDLE") (pin "A") (pinfunction "A_A") (pintype "passive"))
      (node (ref "U1") (pin "31") (pinfunction "PA10_31") (pintype "bidirectional"))
    )
    (net (code "22") (name "LED_RIGHT") (class "Default")
      (node (ref "LED_RIGHT") (pin "A") (pinfunction "A_A") (pintype "passive"))
      (node (ref "U1") (pin "30") (pinfunction "PA9_30") (pintype "bidirectional"))
    )
    (net (code "23") (name "MOTOR1A") (class "Default")
      (node (ref "SCHRITTMOTOR") (pin "4") (pinfunction "4_4") (pintype "passive"))
      (node (ref "U2") (pin "24") (pinfunction "OUT1A_24") (pintype "output"))
    )
    (net (code "24") (name "MOTOR1B") (class "Default")
      (node (ref "SCHRITTMOTOR") (pin "3") (pinfunction "3_3") (pintype "passive"))
      (node (ref "U2") (pin "21") (pinfunction "OUT1B_21") (pintype "output"))
    )
    (net (code "25") (name "MOTOR2A") (class "Default")
      (node (ref "SCHRITTMOTOR") (pin "2") (pinfunction "2_2") (pintype "passive"))
      (node (ref "U2") (pin "26") (pinfunction "OUT2A_26") (pintype "output"))
    )
    (net (code "26") (name "MOTOR2B") (class "Default")
      (node (ref "SCHRITTMOTOR") (pin "1") (pinfunction "1_1") (pintype "passive"))
      (node (ref "U2") (pin "1") (pinfunction "OUT2B_1") (pintype "output"))
    )
    (net (code "27") (name "Net-(IC1-PROG)") (class "Default")
      (node (ref "IC1") (pin "5") (pinfunction "PROG_5") (pintype "bidirectional"))
      (node (ref "R6") (pin "2") (pinfunction "2_2") (pintype "passive"))
    )
    (net (code "28") (name "Net-(IC1-~{CHRG})") (class "Default")
      (node (ref "IC1") (pin "1") (pinfunction "~{CHRG}_1") (pintype "bidirectional"))
      (node (ref "LED2") (pin "C") (pinfunction "C_C") (pintype "passive"))
      (node (ref "Q2") (pin "1") (pinfunction "G_1") (pintype "passive"))
      (node (ref "R8") (pin "2") (pinfunction "2_2") (pintype "passive"))
    )
    (net (code "29") (name "Net-(IC4--IN1)") (class "Default")
      (node (ref "IC4") (pin "2") (pinfunction "-IN1_2") (pintype "input"))
      (node (ref "R27") (pin "1") (pinfunction "1_1") (pintype "passive"))
      (node (ref "R28") (pin "3") (pinfunction "E_3") (pintype "passive"))
    )
    (net (code "30") (name "Net-(LED-PadC)") (class "Default")
      (node (ref "LED") (pin "C") (pinfunction "C_C") (pintype "passive"))
      (node (ref "R5") (pin "2") (pinfunction "2_2") (pintype "passive"))
    )
    (net (code "31") (name "Net-(LED1-PadA)") (class "Default")
      (node (ref "LED1") (pin "A") (pinfunction "A_A") (pintype "passive"))
      (node (ref "LED2") (pin "A") (pinfunction "A_A") (pintype "passive"))
      (node (ref "R7") (pin "2") (pinfunction "2_2") (pintype "passive"))
    )
    (net (code "32") (name "Net-(LED_LEFT-PadC)") (class "Default")
      (node (ref "LED_LEFT") (pin "C") (pinfunction "C_C") (pintype "passive"))
      (node (ref "R30") (pin "2") (pinfunction "2_2") (pintype "passive"))
    )
    (net (code "33") (name "Net-(LED_MIDDLE-PadC)") (class "Default")
      (node (ref "LED_MIDDLE") (pin "C") (pinfunction "C_C") (pintype "passive"))
      (node (ref "R32") (pin "2") (pinfunction "2_2") (pintype "passive"))
    )
    (net (code "34") (name "Net-(LED_RIGHT-PadC)") (class "Default")
      (node (ref "LED_RIGHT") (pin "C") (pinfunction "C_C") (pintype "passive"))
      (node (ref "R31") (pin "2") (pinfunction "2_2") (pintype "passive"))
    )
    (net (code "35") (name "Net-(POWER_LED-PadC)") (class "Default")
      (node (ref "POWER_LED") (pin "C") (pinfunction "C_C") (pintype "passive"))
      (node (ref "R1") (pin "1") (pinfunction "1_1") (pintype "passive"))
    )
    (net (code "36") (name "Net-(PS1-FB)") (class "Default")
      (node (ref "PS1") (pin "5") (pinfunction "FB_5") (pintype "bidirectional"))
      (node (ref "R14") (pin "1") (pinfunction "1_1") (pintype "passive"))
      (node (ref "R15") (pin "2") (pinfunction "2_2") (pintype "passive"))
    )
    (net (code "37") (name "Net-(PS1-PG)") (class "Default")
      (node (ref "PS1") (pin "7") (pinfunction "PG_7") (pintype "bidirectional"))
      (node (ref "R16") (pin "2") (pinfunction "2_2") (pintype "passive"))
    )
    (net (code "38") (name "Net-(PS1-SS{slash}TR)") (class "Default")
      (node (ref "C3") (pin "1") (pinfunction "1_1") (pintype "passive"))
      (node (ref "PS1") (pin "9") (pinfunction "SS/TR_9") (pintype "bidirectional"))
    )
    (net (code "39") (name "Net-(PS1-SW)") (class "Default")
      (node (ref "L1") (pin "2") (pinfunction "2_2") (pintype "bidirectional"))
      (node (ref "PS1") (pin "2") (pinfunction "SW_2") (pintype "bidirectional"))
    )
    (net (code "40") (name "Net-(Q2-S)") (class "Default")
      (node (ref "LED1") (pin "C") (pinfunction "C_C") (pintype "passive"))
      (node (ref "Q2") (pin "2") (pinfunction "S_2") (pintype "passive"))
    )
    (net (code "41") (name "Net-(R3-Pad1)") (class "Default")
      (node (ref "R3") (pin "1") (pinfunction "1_1") (pintype "passive"))
      (node (ref "R4") (pin "2") (pinfunction "2_2") (pintype "passive"))
      (node (ref "S2") (pin "A") (pinfunction "COM_A") (pintype "passive"))
      (node (ref "S2") (pin "B") (pinfunction "COM_B") (pintype "passive"))
    )
    (net (code "42") (name "Net-(R10-Pad2)") (class "Default")
      (node (ref "R10") (pin "2") (pinfunction "2_2") (pintype "passive"))
      (node (ref "R29") (pin "1") (pinfunction "1_1") (pintype "passive"))
      (node (ref "R9") (pin "1") (pinfunction "1_1") (pintype "passive"))
    )
    (net (code "43") (name "Net-(U2-CP1)") (class "Default")
      (node (ref "C18") (pin "2") (pinfunction "2_2") (pintype "passive"))
      (node (ref "U2") (pin "4") (pinfunction "CP1_4") (pintype "passive"))
    )
    (net (code "44") (name "Net-(U2-CP2)") (class "Default")
      (node (ref "C18") (pin "1") (pinfunction "1_1") (pintype "passive"))
      (node (ref "U2") (pin "5") (pinfunction "CP2_5") (pintype "passive"))
    )
    (net (code "45") (name "Net-(U2-ROSC)") (class "Default")
      (node (ref "R20") (pin "2") (pinfunction "2_2") (pintype "passive"))
      (node (ref "U2") (pin "13") (pinfunction "ROSC_13") (pintype "input"))
      (node (ref "U2") (pin "23") (pinfunction "SENSE1_23") (pintype "input"))
      (node (ref "U2") (pin "27") (pinfunction "SENSE2_27") (pintype "input"))
    )
    (net (code "46") (name "Net-(U2-VCP)") (class "Default")
      (node (ref "C16") (pin "2") (pinfunction "2_2") (pintype "passive"))
      (node (ref "U2") (pin "6") (pinfunction "VCP_6") (pintype "passive"))
    )
    (net (code "47") (name "Net-(U2-VREG)") (class "Default")
      (node (ref "C15") (pin "1") (pinfunction "1_1") (pintype "passive"))
      (node (ref "U2") (pin "8") (pinfunction "VREG_8") (pintype "passive"))
    )
    (net (code "48") (name "Net-(USB-B-D+)") (class "Default")
      (node (ref "R25") (pin "2") (pinfunction "2_2") (pintype "passive"))
      (node (ref "USB-B") (pin "3") (pinfunction "D+_3") (pintype "bidirectional"))
    )
    (net (code "49") (name "Net-(USB-B-D-)") (class "Default")
      (node (ref "R26") (pin "2") (pinfunction "2_2") (pintype "passive"))
      (node (ref "USB-B") (pin "2") (pinfunction "D-_2") (pintype "bidirectional"))
    )
    (net (code "50") (name "Net-(X1B-KL)") (class "Default")
      (node (ref "C27") (pin "1") (pinfunction "1_1") (pintype "passive"))
      (node (ref "D12") (pin "A") (pinfunction "A_A") (pintype "passive"))
      (node (ref "D13") (pin "2") (pinfunction "2_2") (pintype "passive"))
      (node (ref "X1") (pin "2") (pinfunction "KL_2") (pintype "passive"))
    )
    (net (code "51") (name "OSC32IN") (class "Default")
      (node (ref "C10") (pin "2") (pinfunction "2_2") (pintype "passive"))
      (node (ref "Q1") (pin "2") (pinfunction "2_2") (pintype "passive"))
      (node (ref "R37") (pin "2") (pinfunction "2_2") (pintype "passive"))
      (node (ref "U1") (pin "3") (pinfunction "PC14-OSC32_IN_3") (pintype "bidirectional"))
    )
    (net (code "52") (name "OSC32OUT") (class "Default")
      (node (ref "C11") (pin "2") (pinfunction "2_2") (pintype "passive"))
      (node (ref "Q1") (pin "1") (pinfunction "1_1") (pintype "passive"))
      (node (ref "R37") (pin "1") (pinfunction "1_1") (pintype "passive"))
      (node (ref "U1") (pin "4") (pinfunction "PC15-OSC32_OUT_4") (pintype "bidirectional"))
    )
    (net (code "53") (name "OSCIN") (class "Default")
      (node (ref "C8") (pin "2") (pinfunction "2_2") (pintype "passive"))
      (node (ref "R12") (pin "2") (pinfunction "2_2") (pintype "passive"))
      (node (ref "U1") (pin "5") (pinfunction "PD0_OSC_IN_5") (pintype "bidirectional"))
      (node (ref "Y1") (pin "2") (pinfunction "2_2") (pintype "passive"))
    )
    (net (code "54") (name "OSCOUT") (class "Default")
      (node (ref "C9") (pin "2") (pinfunction "2_2") (pintype "passive"))
      (node (ref "R12") (pin "1") (pinfunction "1_1") (pintype "passive"))
      (node (ref "U1") (pin "6") (pinfunction "PD1_OSC_OUT_6") (pintype "bidirectional"))
      (node (ref "Y1") (pin "1") (pinfunction "1_1") (pintype "passive"))
    )
    (net (code "55") (name "PC13") (class "Default")
      (node (ref "LED") (pin "A") (pinfunction "A_A") (pintype "passive"))
      (node (ref "U1") (pin "2") (pinfunction "PC13-TAMPER-RTC_2") (pintype "bidirectional"))
    )
    (net (code "56") (name "RESET") (class "Default")
      (node (ref "C2") (pin "1") (pinfunction "1_1") (pintype "passive"))
      (node (ref "R2") (pin "1") (pinfunction "1_1") (pintype "passive"))
      (node (ref "RESET") (pin "C") (pinfunction "NO_C") (pintype "passive"))
      (node (ref "RESET") (pin "D") (pinfunction "NO_D") (pintype "passive"))
      (node (ref "U1") (pin "7") (pinfunction "NRST_7") (pintype "input"))
    )
    (net (code "57") (name "SIGNAL_IN") (class "Default")
      (node (ref "AUDIO_JACK") (pin "2") (pinfunction "RING_1_2") (pintype "passive"))
      (node (ref "AUDIO_JACK") (pin "5") (pinfunction "TIP_2_5") (pintype "passive"))
      (node (ref "IC4") (pin "3") (pinfunction "+IN1_3") (pintype "bidirectional"))
      (node (ref "JP5") (pin "1") (pinfunction "1_1") (pintype "passive"))
    )
    (net (code "58") (name "SIGNAL_OPAMP") (class "Default")
      (node (ref "IC4") (pin "1") (pinfunction "OUT1_1") (pintype "input"))
      (node (ref "JP6") (pin "1") (pinfunction "1_1") (pintype "passive"))
      (node (ref "R27") (pin "2") (pinfunction "2_2") (pintype "passive"))
      (node (ref "U1") (pin "10") (pinfunction "PA0_WKUP_10") (pintype "bidirectional"))
    )
    (net (code "59") (name "SWDCLK") (class "Default")
      (node (ref "D7") (pin "2") (pinfunction "2_2") (pintype "passive"))
      (node (ref "ST_LINK") (pin "2") (pinfunction "2_2") (pintype "passive"))
      (node (ref "U1") (pin "37") (pinfunction "PA14_37") (pintype "bidirectional"))
    )
    (net (code "60") (name "SWDIO") (class "Default")
      (node (ref "D6") (pin "2") (pinfunction "2_2") (pintype "passive"))
      (node (ref "ST_LINK") (pin "3") (pinfunction "3_3") (pintype "passive"))
      (node (ref "U1") (pin "34") (pinfunction "PA13_34") (pintype "bidirectional"))
    )
    (net (code "61") (name "USB+") (class "Default")
      (node (ref "D4") (pin "2") (pinfunction "2_2") (pintype "passive"))
      (node (ref "R13") (pin "1") (pinfunction "1_1") (pintype "passive"))
      (node (ref "R25") (pin "1") (pinfunction "1_1") (pintype "passive"))
      (node (ref "U1") (pin "33") (pinfunction "PA12_33") (pintype "bidirectional"))
    )
    (net (code "62") (name "USB-") (class "Default")
      (node (ref "D3") (pin "2") (pinfunction "2_2") (pintype "passive"))
      (node (ref "R26") (pin "1") (pinfunction "1_1") (pintype "passive"))
      (node (ref "U1") (pin "32") (pinfunction "PA11_32") (pintype "bidirectional"))
    )
    (net (code "63") (name "VBAT") (class "Default")
      (node (ref "BATTERIE") (pin "2") (pinfunction "2_2") (pintype "passive"))
      (node (ref "IC1") (pin "3") (pinfunction "BAT_3") (pintype "bidirectional"))
      (node (ref "Q3") (pin "2") (pinfunction "S_2") (pintype "passive"))
      (node (ref "R9") (pin "2") (pinfunction "2_2") (pintype "passive"))
    )
    (net (code "64") (name "VIN") (class "Default")
      (node (ref "C5") (pin "1") (pinfunction "1_1") (pintype "passive"))
      (node (ref "D1") (pin "1") (pinfunction "C_1") (pintype "passive"))
      (node (ref "PS1") (pin "1") (pinfunction "VIN_1") (pintype "bidirectional"))
      (node (ref "PS1") (pin "8") (pinfunction "EN_8") (pintype "bidirectional"))
      (node (ref "Q3") (pin "3") (pinfunction "D_3") (pintype "passive"))
    )
    (net (code "65") (name "VKLEMME") (class "Default")
      (node (ref "D1") (pin "2") (pinfunction "A_2") (pintype "passive"))
      (node (ref "D12") (pin "C") (pinfunction "C_C") (pintype "passive"))
      (node (ref "IC1") (pin "4") (pinfunction "VCC_4") (pintype "bidirectional"))
      (node (ref "Q3") (pin "1") (pinfunction "G_1") (pintype "passive"))
      (node (ref "R11") (pin "2") (pinfunction "2_2") (pintype "passive"))
      (node (ref "R7") (pin "1") (pinfunction "1_1") (pintype "passive"))
      (node (ref "R8") (pin "1") (pinfunction "1_1") (pintype "passive"))
    )
    (net (code "66") (name "unconnected-(AUDIO_JACK-RING_2-Pad3)") (class "Default")
      (node (ref "AUDIO_JACK") (pin "3") (pinfunction "RING_2_3") (pintype "passive"))
    )
    (net (code "67") (name "unconnected-(AUDIO_JACK-TIP_1-Pad4)") (class "Default")
      (node (ref "AUDIO_JACK") (pin "4") (pinfunction "TIP_1_4") (pintype "passive"))
    )
    (net (code "68") (name "unconnected-(IC4-+IN2-Pad5)") (class "Default")
      (node (ref "IC4") (pin "5") (pinfunction "+IN2_5") (pintype "passive"))
    )
    (net (code "69") (name "unconnected-(IC4-+IN3-Pad10)") (class "Default")
      (node (ref "IC4") (pin "10") (pinfunction "+IN3_10") (pintype "passive"))
    )
    (net (code "70") (name "unconnected-(IC4-+IN4-Pad12)") (class "Default")
      (node (ref "IC4") (pin "12") (pinfunction "+IN4_12") (pintype "bidirectional"))
    )
    (net (code "71") (name "unconnected-(IC4--IN2-Pad6)") (class "Default")
      (node (ref "IC4") (pin "6") (pinfunction "-IN2_6") (pintype "passive"))
    )
    (net (code "72") (name "unconnected-(IC4--IN3-Pad9)") (class "Default")
      (node (ref "IC4") (pin "9") (pinfunction "-IN3_9") (pintype "passive"))
    )
    (net (code "73") (name "unconnected-(IC4--IN4-Pad13)") (class "Default")
      (node (ref "IC4") (pin "13") (pinfunction "-IN4_13") (pintype "bidirectional"))
    )
    (net (code "74") (name "unconnected-(IC4-OUT2-Pad7)") (class "Default")
      (node (ref "IC4") (pin "7") (pinfunction "OUT2_7") (pintype "passive"))
    )
    (net (code "75") (name "unconnected-(IC4-OUT3-Pad8)") (class "Default")
      (node (ref "IC4") (pin "8") (pinfunction "OUT3_8") (pintype "passive"))
    )
    (net (code "76") (name "unconnected-(IC4-OUT4-Pad14)") (class "Default")
      (node (ref "IC4") (pin "14") (pinfunction "OUT4_14") (pintype "output"))
    )
    (net (code "77") (name "unconnected-(U1-PA1-Pad11)") (class "Default")
      (node (ref "U1") (pin "11") (pinfunction "PA1_11") (pintype "bidirectional"))
    )
    (net (code "78") (name "unconnected-(U1-PA2-Pad12)") (class "Default")
      (node (ref "U1") (pin "12") (pinfunction "PA2_12") (pintype "bidirectional"))
    )
    (net (code "79") (name "unconnected-(U1-PA3-Pad13)") (class "Default")
      (node (ref "U1") (pin "13") (pinfunction "PA3_13") (pintype "bidirectional"))
    )
    (net (code "80") (name "unconnected-(U1-PA7-Pad17)") (class "Default")
      (node (ref "U1") (pin "17") (pinfunction "PA7_17") (pintype "bidirectional"))
    )
    (net (code "81") (name "unconnected-(U1-PB2-Pad20)") (class "Default")
      (node (ref "U1") (pin "20") (pinfunction "PB2_20") (pintype "bidirectional"))
    )
    (net (code "82") (name "unconnected-(U1-PB5-Pad41)") (class "Default")
      (node (ref "U1") (pin "41") (pinfunction "PB5_41") (pintype "bidirectional"))
    )
    (net (code "83") (name "unconnected-(U1-PB8-Pad45)") (class "Default")
      (node (ref "U1") (pin "45") (pinfunction "PB8_45") (pintype "bidirectional"))
    )
    (net (code "84") (name "unconnected-(U1-PB9-Pad46)") (class "Default")
      (node (ref "U1") (pin "46") (pinfunction "PB9_46") (pintype "bidirectional"))
    )
    (net (code "85") (name "unconnected-(U1-PB10-Pad21)") (class "Default")
      (node (ref "U1") (pin "21") (pinfunction "PB10_21") (pintype "bidirectional"))
    )
    (net (code "86") (name "unconnected-(U1-PB12-Pad25)") (class "Default")
      (node (ref "U1") (pin "25") (pinfunction "PB12_25") (pintype "bidirectional"))
    )
    (net (code "87") (name "unconnected-(U2-REF-Pad17)") (class "Default")
      (node (ref "U2") (pin "17") (pinfunction "REF_17") (pintype "input"))
    )
  )
)
